# BaseArduino.net
KiCad netlist of a schematic drawn in Altium Designer
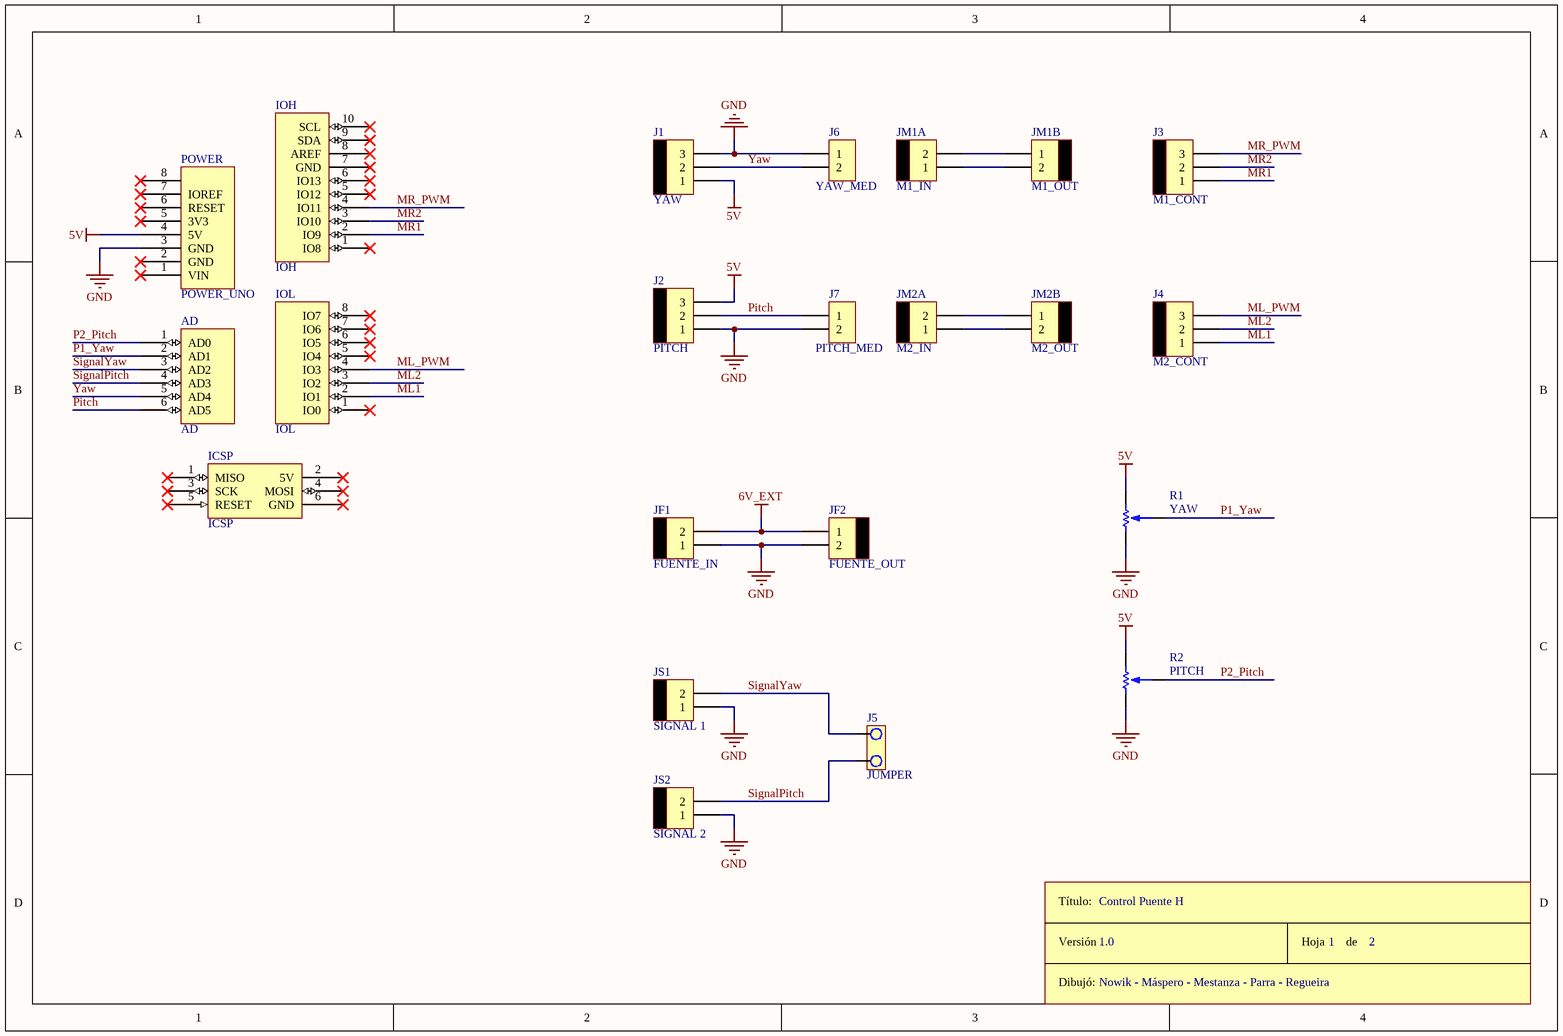
[diagram p0: BaseArduino.SchDoc]

(export (version "E")
  (design (tool "Eeschema 10.0.6"))
  (components
    (comp (ref "AD") (value "AD") (footprint "Header 6x1 8.5mm") (libsource (lib "Headers") (part "AD")))
    (comp (ref "ICSP") (value "ICSP") (footprint "ICSP") (libsource (lib "Headers") (part "ICSP")))
    (comp (ref "IOH") (value "IOH") (footprint "Header 10x1 8.5mm") (libsource (lib "Headers") (part "IOH")))
    (comp (ref "IOL") (value "IOL") (footprint "Header 8x1 8.5mm") (libsource (lib "Headers") (part "IOL")))
    (comp (ref "J1") (value "YAW") (footprint "MOLEX3") (libsource (lib "LIBEBAL") (part "MOLEX3")))
    (comp (ref "J2") (value "PITCH") (footprint "MOLEX3") (libsource (lib "LIBEBAL") (part "MOLEX3")))
    (comp (ref "J3") (value "M1_CONT") (footprint "MOLEX3") (libsource (lib "LIBEBAL") (part "MOLEX3")))
    (comp (ref "J4") (value "M2_CONT") (footprint "MOLEX3") (libsource (lib "LIBEBAL") (part "MOLEX3")))
    (comp (ref "J5") (value "JUMPER") (footprint "JUMPER2") (libsource (lib "LIBEBAL") (part "JUMPER")))
    (comp (ref "J6") (value "YAW_MED") (footprint "SIP2") (libsource (lib "LIBEBAL") (part "CON2")))
    (comp (ref "J7") (value "PITCH_MED") (footprint "SIP2") (libsource (lib "LIBEBAL") (part "CON2")))
    (comp (ref "JF1") (value "FUENTE_IN") (footprint "MOLEX2") (libsource (lib "LIBEBAL") (part "MOLEX2")))
    (comp (ref "JF2") (value "FUENTE_OUT") (footprint "MOLEX2") (libsource (lib "") (part "MOLEX2_1")))
    (comp (ref "JM1A") (value "M1_IN") (footprint "MOLEX2") (libsource (lib "LIBEBAL") (part "MOLEX2")))
    (comp (ref "JM1B") (value "M1_OUT") (footprint "MOLEX2") (libsource (lib "") (part "MOLEX2_1")))
    (comp (ref "JM2A") (value "M2_IN") (footprint "MOLEX2") (libsource (lib "LIBEBAL") (part "MOLEX2")))
    (comp (ref "JM2B") (value "M2_OUT") (footprint "MOLEX2") (libsource (lib "") (part "MOLEX2_1")))
    (comp (ref "JS1") (value "SIGNAL 1") (footprint "MOLEX2") (libsource (lib "LIBEBAL") (part "MOLEX2")))
    (comp (ref "JS2") (value "SIGNAL 2") (footprint "MOLEX2") (libsource (lib "LIBEBAL") (part "MOLEX2")))
    (comp (ref "POWER")
      (value "POWER_UNO")
      (footprint "Header 8x1 8.5mm")
      (libsource (lib "Headers") (part "POWER_UNO"))
    )
    (comp (ref "R1")
      (value "YAW")
      (footprint "POTENCIOMETRO")
      (libsource (lib "LIBEBAL") (part "POTENCIOMETRO"))
    )
    (comp (ref "R2")
      (value "PITCH")
      (footprint "POTENCIOMETRO")
      (libsource (lib "LIBEBAL") (part "POTENCIOMETRO"))
    )
    (comp (ref "ROT1") (value "Rótulo") (libsource (lib "LIB PIO IX") (part "Rótulo")))
  )
  (nets
    (net (code "1") (name "/ML1") (class "Default")
      (node (ref "IOL") (pin "2") (pinfunction "IO1_2") (pintype "bidirectional"))
      (node (ref "J4") (pin "1") (pinfunction "1_1") (pintype "passive"))
    )
    (net (code "2") (name "/ML2") (class "Default")
      (node (ref "IOL") (pin "3") (pinfunction "IO2_3") (pintype "bidirectional"))
      (node (ref "J4") (pin "2") (pinfunction "2_2") (pintype "passive"))
    )
    (net (code "3") (name "/ML_PWM") (class "Default")
      (node (ref "IOL") (pin "4") (pinfunction "IO3_4") (pintype "bidirectional"))
      (node (ref "J4") (pin "3") (pinfunction "3_3") (pintype "passive"))
    )
    (net (code "4") (name "/MR1") (class "Default")
      (node (ref "IOH") (pin "2") (pinfunction "IO9_2") (pintype "bidirectional"))
      (node (ref "J3") (pin "1") (pinfunction "1_1") (pintype "passive"))
    )
    (net (code "5") (name "/MR2") (class "Default")
      (node (ref "IOH") (pin "3") (pinfunction "IO10_3") (pintype "bidirectional"))
      (node (ref "J3") (pin "2") (pinfunction "2_2") (pintype "passive"))
    )
    (net (code "6") (name "/MR_PWM") (class "Default")
      (node (ref "IOH") (pin "4") (pinfunction "IO11_4") (pintype "bidirectional"))
      (node (ref "J3") (pin "3") (pinfunction "3_3") (pintype "passive"))
    )
    (net (code "7") (name "/P1_Yaw") (class "Default")
      (node (ref "AD") (pin "2") (pinfunction "AD1_2") (pintype "bidirectional"))
      (node (ref "R1") (pin "2") (pinfunction "2_2") (pintype "passive"))
    )
    (net (code "8") (name "/P2_Pitch") (class "Default")
      (node (ref "AD") (pin "1") (pinfunction "AD0_1") (pintype "bidirectional"))
      (node (ref "R2") (pin "2") (pinfunction "2_2") (pintype "passive"))
    )
    (net (code "9") (name "/Pitch") (class "Default")
      (node (ref "AD") (pin "6") (pinfunction "AD5_6") (pintype "bidirectional"))
      (node (ref "J2") (pin "2") (pinfunction "2_2") (pintype "passive"))
      (node (ref "J7") (pin "1") (pinfunction "1_1") (pintype "passive"))
    )
    (net (code "10") (name "/SignalPitch") (class "Default")
      (node (ref "AD") (pin "4") (pinfunction "AD3_4") (pintype "bidirectional"))
      (node (ref "J5") (pin "1") (pinfunction "1_1") (pintype "passive"))
      (node (ref "JS2") (pin "2") (pinfunction "2_2") (pintype "passive"))
    )
    (net (code "11") (name "/SignalYaw") (class "Default")
      (node (ref "AD") (pin "3") (pinfunction "AD2_3") (pintype "bidirectional"))
      (node (ref "J5") (pin "2") (pinfunction "2_2") (pintype "passive"))
      (node (ref "JS1") (pin "2") (pinfunction "2_2") (pintype "passive"))
    )
    (net (code "12") (name "/Yaw") (class "Default")
      (node (ref "AD") (pin "5") (pinfunction "AD4_5") (pintype "bidirectional"))
      (node (ref "J1") (pin "2") (pinfunction "2_2") (pintype "passive"))
      (node (ref "J6") (pin "2") (pinfunction "2_2") (pintype "passive"))
    )
    (net (code "13") (name "5V") (class "Default")
      (node (ref "J1") (pin "1") (pinfunction "1_1") (pintype "passive"))
      (node (ref "J2") (pin "3") (pinfunction "3_3") (pintype "passive"))
      (node (ref "POWER") (pin "4") (pinfunction "5V_4") (pintype "power_in"))
      (node (ref "R1") (pin "1") (pinfunction "1_1") (pintype "passive"))
      (node (ref "R2") (pin "1") (pinfunction "1_1") (pintype "passive"))
    )
    (net (code "14") (name "6V_EXT") (class "Default")
      (node (ref "JF1") (pin "2") (pinfunction "2_2") (pintype "passive"))
      (node (ref "JF2") (pin "1") (pinfunction "1_1") (pintype "passive"))
    )
    (net (code "15") (name "GND") (class "Default")
      (node (ref "J1") (pin "3") (pinfunction "3_3") (pintype "passive"))
      (node (ref "J2") (pin "1") (pinfunction "1_1") (pintype "passive"))
      (node (ref "J6") (pin "1") (pinfunction "1_1") (pintype "passive"))
      (node (ref "J7") (pin "2") (pinfunction "2_2") (pintype "passive"))
      (node (ref "JF1") (pin "1") (pinfunction "1_1") (pintype "passive"))
      (node (ref "JF2") (pin "2") (pinfunction "2_2") (pintype "passive"))
      (node (ref "JS1") (pin "1") (pinfunction "1_1") (pintype "passive"))
      (node (ref "JS2") (pin "1") (pinfunction "1_1") (pintype "passive"))
      (node (ref "POWER") (pin "3") (pinfunction "GND_3") (pintype "power_in"))
      (node (ref "R1") (pin "3") (pinfunction "3_3") (pintype "passive"))
      (node (ref "R2") (pin "3") (pinfunction "3_3") (pintype "passive"))
    )
    (net (code "16") (name "Net-(JM1A-Pad1)") (class "Default")
      (node (ref "JM1A") (pin "1") (pinfunction "1_1") (pintype "passive"))
      (node (ref "JM1B") (pin "2") (pinfunction "2_2") (pintype "passive"))
    )
    (net (code "17") (name "Net-(JM1A-Pad2)") (class "Default")
      (node (ref "JM1A") (pin "2") (pinfunction "2_2") (pintype "passive"))
      (node (ref "JM1B") (pin "1") (pinfunction "1_1") (pintype "passive"))
    )
    (net (code "18") (name "Net-(JM2A-Pad1)") (class "Default")
      (node (ref "JM2A") (pin "1") (pinfunction "1_1") (pintype "passive"))
      (node (ref "JM2B") (pin "2") (pinfunction "2_2") (pintype "passive"))
    )
    (net (code "19") (name "Net-(JM2A-Pad2)") (class "Default")
      (node (ref "JM2A") (pin "2") (pinfunction "2_2") (pintype "passive"))
      (node (ref "JM2B") (pin "1") (pinfunction "1_1") (pintype "passive"))
    )
    (net (code "20") (name "unconnected-(ICSP-5V-Pad2)") (class "Default")
      (node (ref "ICSP") (pin "2") (pinfunction "5V_2") (pintype "power_in+no_connect"))
    )
    (net (code "21") (name "unconnected-(ICSP-GND-Pad6)") (class "Default")
      (node (ref "ICSP") (pin "6") (pinfunction "GND_6") (pintype "power_in+no_connect"))
    )
    (net (code "22") (name "unconnected-(ICSP-MISO-Pad1)") (class "Default")
      (node (ref "ICSP") (pin "1") (pinfunction "MISO_1") (pintype "bidirectional+no_connect"))
    )
    (net (code "23") (name "unconnected-(ICSP-MOSI-Pad4)") (class "Default")
      (node (ref "ICSP") (pin "4") (pinfunction "MOSI_4") (pintype "bidirectional+no_connect"))
    )
    (net (code "24") (name "unconnected-(ICSP-RESET-Pad5)") (class "Default")
      (node (ref "ICSP") (pin "5") (pinfunction "RESET_5") (pintype "input+no_connect"))
    )
    (net (code "25") (name "unconnected-(ICSP-SCK-Pad3)") (class "Default")
      (node (ref "ICSP") (pin "3") (pinfunction "SCK_3") (pintype "bidirectional+no_connect"))
    )
    (net (code "26") (name "unconnected-(IOH-AREF-Pad8)") (class "Default")
      (node (ref "IOH") (pin "8") (pinfunction "AREF_8") (pintype "passive+no_connect"))
    )
    (net (code "27") (name "unconnected-(IOH-GND-Pad7)") (class "Default")
      (node (ref "IOH") (pin "7") (pinfunction "GND_7") (pintype "power_in+no_connect"))
    )
    (net (code "28") (name "unconnected-(IOH-IO8-Pad1)") (class "Default")
      (node (ref "IOH") (pin "1") (pinfunction "IO8_1") (pintype "bidirectional+no_connect"))
    )
    (net (code "29") (name "unconnected-(IOH-IO12-Pad5)") (class "Default")
      (node (ref "IOH") (pin "5") (pinfunction "IO12_5") (pintype "bidirectional+no_connect"))
    )
    (net (code "30") (name "unconnected-(IOH-IO13-Pad6)") (class "Default")
      (node (ref "IOH") (pin "6") (pinfunction "IO13_6") (pintype "bidirectional+no_connect"))
    )
    (net (code "31") (name "unconnected-(IOH-SCL-Pad10)") (class "Default")
      (node (ref "IOH") (pin "10") (pinfunction "SCL_10") (pintype "bidirectional+no_connect"))
    )
    (net (code "32") (name "unconnected-(IOH-SDA-Pad9)") (class "Default")
      (node (ref "IOH") (pin "9") (pinfunction "SDA_9") (pintype "bidirectional+no_connect"))
    )
    (net (code "33") (name "unconnected-(IOL-IO0-Pad1)") (class "Default")
      (node (ref "IOL") (pin "1") (pinfunction "IO0_1") (pintype "bidirectional+no_connect"))
    )
    (net (code "34") (name "unconnected-(IOL-IO4-Pad5)") (class "Default")
      (node (ref "IOL") (pin "5") (pinfunction "IO4_5") (pintype "bidirectional+no_connect"))
    )
    (net (code "35") (name "unconnected-(IOL-IO5-Pad6)") (class "Default")
      (node (ref "IOL") (pin "6") (pinfunction "IO5_6") (pintype "bidirectional+no_connect"))
    )
    (net (code "36") (name "unconnected-(IOL-IO6-Pad7)") (class "Default")
      (node (ref "IOL") (pin "7") (pinfunction "IO6_7") (pintype "bidirectional+no_connect"))
    )
    (net (code "37") (name "unconnected-(IOL-IO7-Pad8)") (class "Default")
      (node (ref "IOL") (pin "8") (pinfunction "IO7_8") (pintype "bidirectional+no_connect"))
    )
    (net (code "38") (name "unconnected-(POWER-3V3-Pad5)") (class "Default")
      (node (ref "POWER") (pin "5") (pinfunction "3V3_5") (pintype "power_in+no_connect"))
    )
    (net (code "39") (name "unconnected-(POWER-GND-Pad2)") (class "Default")
      (node (ref "POWER") (pin "2") (pinfunction "GND_2") (pintype "power_in+no_connect"))
    )
    (net (code "40") (name "unconnected-(POWER-IOREF-Pad7)") (class "Default")
      (node (ref "POWER") (pin "7") (pinfunction "IOREF_7") (pintype "power_in+no_connect"))
    )
    (net (code "41") (name "unconnected-(POWER-Pad8)") (class "Default")
      (node (ref "POWER") (pin "8") (pintype "passive+no_connect"))
    )
    (net (code "42") (name "unconnected-(POWER-RESET-Pad6)") (class "Default")
      (node (ref "POWER") (pin "6") (pinfunction "RESET_6") (pintype "passive+no_connect"))
    )
    (net (code "43") (name "unconnected-(POWER-VIN-Pad1)") (class "Default")
      (node (ref "POWER") (pin "1") (pinfunction "VIN_1") (pintype "power_in+no_connect"))
    )
  )
)
